# CKP_CMP.net
KiCad netlist of a schematic drawn in Altium Designer
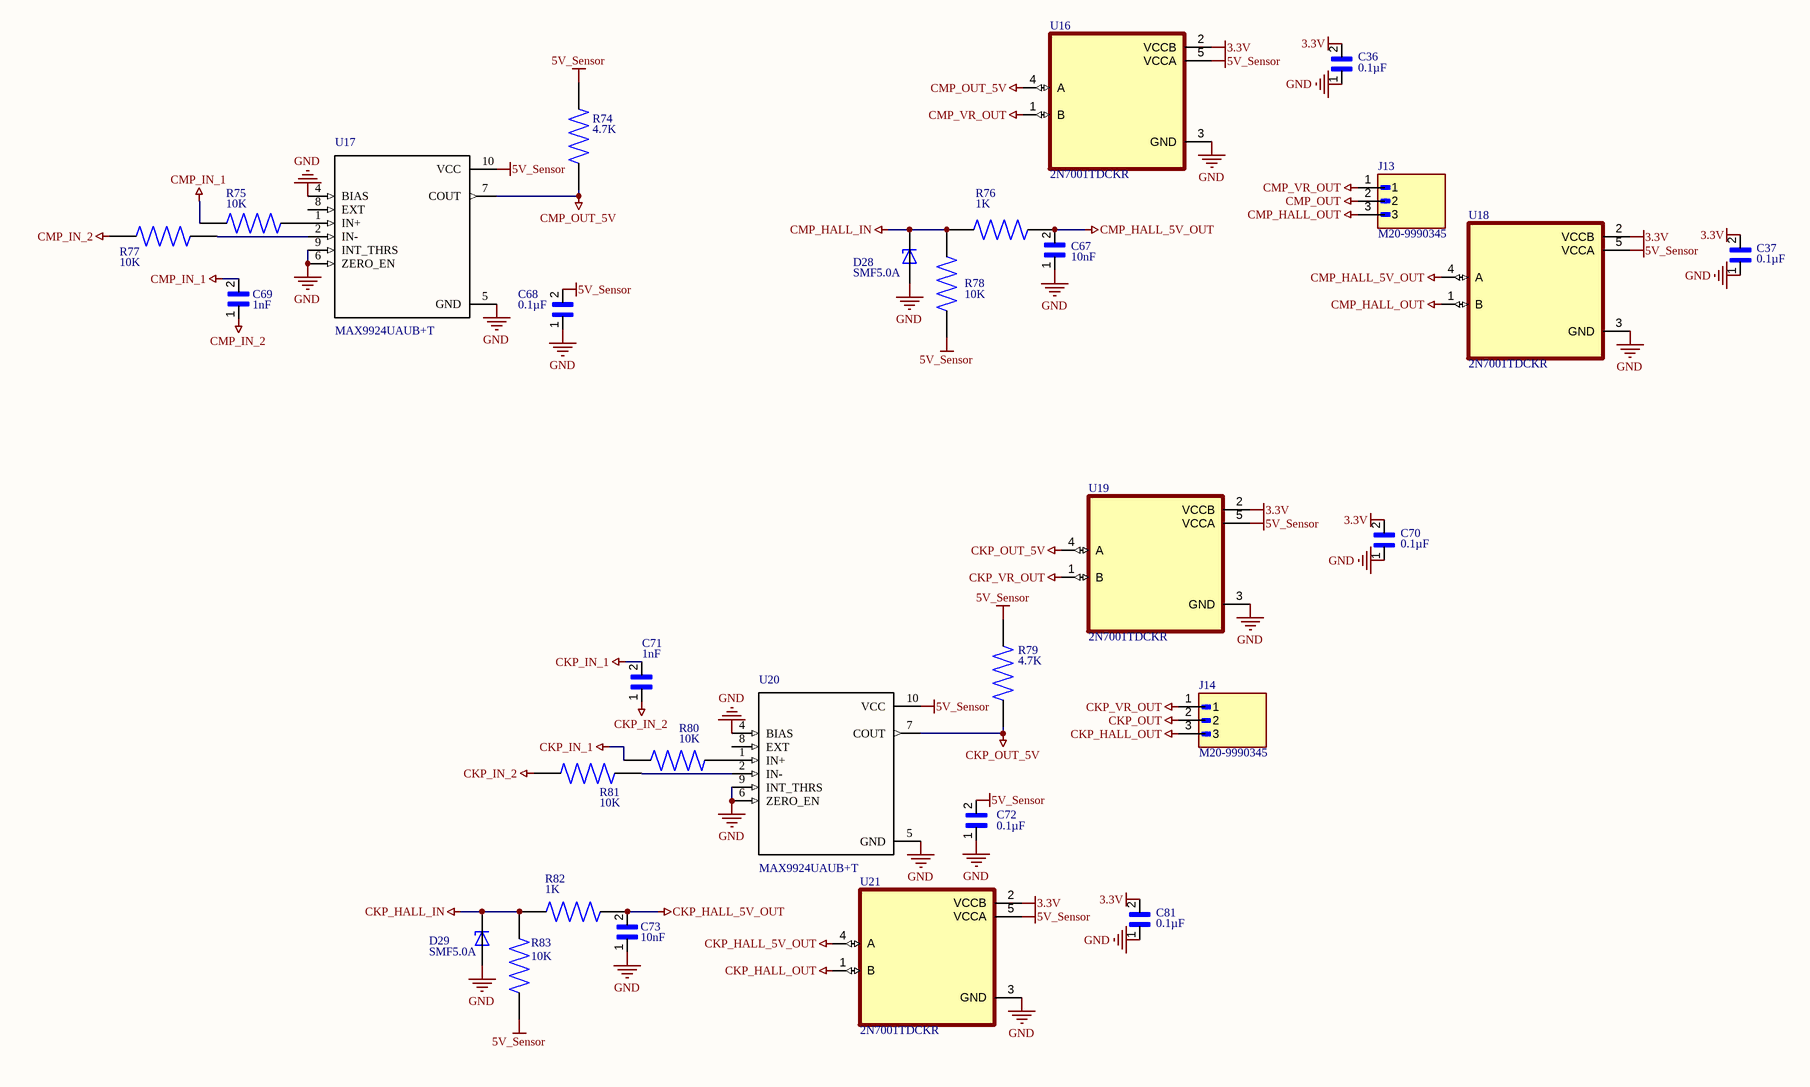
[diagram p0: CKP_CMP.SchDoc]

(export (version "E")
  (design (tool "Eeschema 10.0.6"))
  (components
    (comp (ref "C36")
      (value "0.1µF")
      (footprint "CAPC1608X90N")
      (description "Multilayer Ceramic Capacitors MLCC - SMD/SMT")
      (fields (field (name "MP") "06035C104MAZ2A"))
      (libsource (lib "06035C104MAZ2A") (part "06035C104MAZ2A"))
    )
    (comp (ref "C37")
      (value "0.1µF")
      (footprint "CAPC1608X90N")
      (description "Multilayer Ceramic Capacitors MLCC - SMD/SMT")
      (fields (field (name "MP") "06035C104MAZ2A"))
      (libsource (lib "06035C104MAZ2A") (part "06035C104MAZ2A"))
    )
    (comp (ref "C67")
      (value "10nF")
      (footprint "CAPC1608X90N")
      (description "Multilayer Ceramic Capacitors MLCC - SMD/SMT")
      (fields (field (name "MP") "06035C104MAZ2A"))
      (libsource (lib "06035C104MAZ2A") (part "06035C104MAZ2A"))
    )
    (comp (ref "C68")
      (value "0.1µF")
      (footprint "CAPC1608X90N")
      (description "Multilayer Ceramic Capacitors MLCC - SMD/SMT")
      (fields (field (name "MP") "06035C104MAZ2A"))
      (libsource (lib "06035C104MAZ2A") (part "06035C104MAZ2A"))
    )
    (comp (ref "C69")
      (value "1nF")
      (footprint "CAPC1608X90N")
      (description "Multilayer Ceramic Capacitors MLCC - SMD/SMT")
      (fields (field (name "MP") "06035C104MAZ2A"))
      (libsource (lib "06035C104MAZ2A") (part "06035C104MAZ2A"))
    )
    (comp (ref "C70")
      (value "0.1µF")
      (footprint "CAPC1608X90N")
      (description "Multilayer Ceramic Capacitors MLCC - SMD/SMT")
      (fields (field (name "MP") "06035C104MAZ2A"))
      (libsource (lib "06035C104MAZ2A") (part "06035C104MAZ2A"))
    )
    (comp (ref "C71")
      (value "1nF")
      (footprint "CAPC1608X90N")
      (description "Multilayer Ceramic Capacitors MLCC - SMD/SMT")
      (fields (field (name "MP") "06035C104MAZ2A"))
      (libsource (lib "06035C104MAZ2A") (part "06035C104MAZ2A"))
    )
    (comp (ref "C72")
      (value "0.1µF")
      (footprint "CAPC1608X90N")
      (description "Multilayer Ceramic Capacitors MLCC - SMD/SMT")
      (fields (field (name "MP") "06035C104MAZ2A"))
      (libsource (lib "06035C104MAZ2A") (part "06035C104MAZ2A"))
    )
    (comp (ref "C73")
      (value "10nF")
      (footprint "CAPC1608X90N")
      (description "Multilayer Ceramic Capacitors MLCC - SMD/SMT")
      (fields (field (name "MP") "06035C104MAZ2A"))
      (libsource (lib "06035C104MAZ2A") (part "06035C104MAZ2A"))
    )
    (comp (ref "C81")
      (value "0.1µF")
      (footprint "CAPC1608X90N")
      (description "Multilayer Ceramic Capacitors MLCC - SMD/SMT")
      (fields (field (name "MP") "06035C104MAZ2A"))
      (libsource (lib "06035C104MAZ2A") (part "06035C104MAZ2A"))
    )
    (comp (ref "D28")
      (value "SMF5.0A")
      (footprint "SODFL3718X102N")
      (description "200W, 6.7V, 5%, Unidirectional, TVS")
      (fields (field (name "MF") "Taiwan Semiconductor"))
      (libsource (lib "SMF5.0A") (part "SMF5.0A"))
    )
    (comp (ref "D29")
      (value "SMF5.0A")
      (footprint "SODFL3718X102N")
      (description "200W, 6.7V, 5%, Unidirectional, TVS")
      (fields (field (name "MF") "Taiwan Semiconductor"))
      (libsource (lib "SMF5.0A") (part "SMF5.0A"))
    )
    (comp (ref "J13")
      (value "M20-9990345")
      (footprint "HARWIN_M20-9990345")
      (fields (field (name "MF") "Harwin"))
      (libsource (lib "M20-9990345") (part "M20-9990345"))
    )
    (comp (ref "J14")
      (value "M20-9990345")
      (footprint "HARWIN_M20-9990345")
      (fields (field (name "MF") "Harwin"))
      (libsource (lib "M20-9990345") (part "M20-9990345"))
    )
    (comp (ref "R74")
      (value "4.7K")
      (footprint "RESC3116X65N")
      (fields (field (name "MP") "AA1206JR-07470RL"))
      (libsource (lib "AA1206JR-07470RL") (part "AA1206JR-07470RL"))
    )
    (comp (ref "R75")
      (value "10K")
      (footprint "RESC3116X65N")
      (fields (field (name "MP") "AA1206JR-07470RL"))
      (libsource (lib "AA1206JR-07470RL") (part "AA1206JR-07470RL"))
    )
    (comp (ref "R76")
      (value "1K")
      (footprint "RESC3116X65N")
      (fields (field (name "MP") "AA1206JR-07470RL"))
      (libsource (lib "AA1206JR-07470RL") (part "AA1206JR-07470RL"))
    )
    (comp (ref "R77")
      (value "10K")
      (footprint "RESC3116X65N")
      (fields (field (name "MP") "AA1206JR-07470RL"))
      (libsource (lib "AA1206JR-07470RL") (part "AA1206JR-07470RL"))
    )
    (comp (ref "R78")
      (value "10K")
      (footprint "RESC3116X65N")
      (fields (field (name "MP") "AA1206JR-07470RL"))
      (libsource (lib "AA1206JR-07470RL") (part "AA1206JR-07470RL"))
    )
    (comp (ref "R79")
      (value "4.7K")
      (footprint "RESC3116X65N")
      (fields (field (name "MP") "AA1206JR-07470RL"))
      (libsource (lib "AA1206JR-07470RL") (part "AA1206JR-07470RL"))
    )
    (comp (ref "R80")
      (value "10K")
      (footprint "RESC3116X65N")
      (fields (field (name "MP") "AA1206JR-07470RL"))
      (libsource (lib "AA1206JR-07470RL") (part "AA1206JR-07470RL"))
    )
    (comp (ref "R81")
      (value "10K")
      (footprint "RESC3116X65N")
      (fields (field (name "MP") "AA1206JR-07470RL"))
      (libsource (lib "AA1206JR-07470RL") (part "AA1206JR-07470RL"))
    )
    (comp (ref "R82")
      (value "1K")
      (footprint "RESC3116X65N")
      (fields (field (name "MP") "AA1206JR-07470RL"))
      (libsource (lib "AA1206JR-07470RL") (part "AA1206JR-07470RL"))
    )
    (comp (ref "R83")
      (value "10K")
      (footprint "RESC3116X65N")
      (fields (field (name "MP") "AA1206JR-07470RL"))
      (libsource (lib "AA1206JR-07470RL") (part "AA1206JR-07470RL"))
    )
    (comp (ref "U16")
      (value "2N7001TDCKR")
      (footprint "SOT65P210X110-5N")
      (description "1-bit dual-supply buffered voltage signal converter")
      (fields (field (name "MF") "Texas Instruments"))
      (libsource (lib "2N7001TDCKR") (part "2N7001TDCKR"))
    )
    (comp (ref "U17")
      (value "MAX9924UAUB+T")
      (footprint "*SOP50P490X110-10N")
      (libsource (lib "MAX9924UAUB_T") (part "MAX9924UAUB+T"))
    )
    (comp (ref "U18")
      (value "2N7001TDCKR")
      (footprint "SOT65P210X110-5N")
      (description "1-bit dual-supply buffered voltage signal converter")
      (fields (field (name "MF") "Texas Instruments"))
      (libsource (lib "2N7001TDCKR") (part "2N7001TDCKR"))
    )
    (comp (ref "U19")
      (value "2N7001TDCKR")
      (footprint "SOT65P210X110-5N")
      (description "1-bit dual-supply buffered voltage signal converter")
      (fields (field (name "MF") "Texas Instruments"))
      (libsource (lib "2N7001TDCKR") (part "2N7001TDCKR"))
    )
    (comp (ref "U20")
      (value "MAX9924UAUB+T")
      (footprint "*SOP50P490X110-10N")
      (libsource (lib "MAX9924UAUB_T") (part "MAX9924UAUB+T"))
    )
    (comp (ref "U21")
      (value "2N7001TDCKR")
      (footprint "SOT65P210X110-5N")
      (description "1-bit dual-supply buffered voltage signal converter")
      (fields (field (name "MF") "Texas Instruments"))
      (libsource (lib "2N7001TDCKRa") (part "2N7001TDCKR"))
    )
  )
  (nets
    (net (code "1") (name "3.3V") (class "Default")
      (node (ref "C36") (pin "2") (pinfunction "2_2") (pintype "passive"))
      (node (ref "C37") (pin "2") (pinfunction "2_2") (pintype "passive"))
      (node (ref "C70") (pin "2") (pinfunction "2_2") (pintype "passive"))
      (node (ref "C81") (pin "2") (pinfunction "2_2") (pintype "passive"))
      (node (ref "U16") (pin "2") (pinfunction "VCCB_2") (pintype "power_in"))
      (node (ref "U18") (pin "2") (pinfunction "VCCB_2") (pintype "power_in"))
      (node (ref "U19") (pin "2") (pinfunction "VCCB_2") (pintype "power_in"))
      (node (ref "U21") (pin "2") (pinfunction "VCCB_2") (pintype "power_in"))
    )
    (net (code "2") (name "5V_Sensor") (class "Default")
      (node (ref "C68") (pin "2") (pinfunction "2_2") (pintype "passive"))
      (node (ref "C72") (pin "2") (pinfunction "2_2") (pintype "passive"))
      (node (ref "R74") (pin "2") (pinfunction "2_2") (pintype "passive"))
      (node (ref "R78") (pin "1") (pinfunction "1_1") (pintype "passive"))
      (node (ref "R79") (pin "2") (pinfunction "2_2") (pintype "passive"))
      (node (ref "R83") (pin "1") (pinfunction "1_1") (pintype "passive"))
      (node (ref "U16") (pin "5") (pinfunction "VCCA_5") (pintype "power_in"))
      (node (ref "U17") (pin "10") (pinfunction "VCC_10") (pintype "power_in"))
      (node (ref "U18") (pin "5") (pinfunction "VCCA_5") (pintype "power_in"))
      (node (ref "U19") (pin "5") (pinfunction "VCCA_5") (pintype "power_in"))
      (node (ref "U20") (pin "10") (pinfunction "VCC_10") (pintype "power_in"))
      (node (ref "U21") (pin "5") (pinfunction "VCCA_5") (pintype "power_in"))
    )
    (net (code "3") (name "CKP_HALL_5V_OUT") (class "Default")
      (node (ref "C73") (pin "2") (pinfunction "2_2") (pintype "passive"))
      (node (ref "R82") (pin "1") (pinfunction "1_1") (pintype "passive"))
      (node (ref "U21") (pin "4") (pinfunction "A_4") (pintype "bidirectional"))
    )
    (net (code "4") (name "CKP_HALL_IN") (class "Default")
      (node (ref "D29") (pin "C") (pinfunction "C_C") (pintype "passive"))
      (node (ref "R82") (pin "2") (pinfunction "2_2") (pintype "passive"))
      (node (ref "R83") (pin "2") (pinfunction "2_2") (pintype "passive"))
    )
    (net (code "5") (name "CKP_HALL_OUT") (class "Default")
      (node (ref "J14") (pin "3") (pinfunction "3_3") (pintype "passive"))
      (node (ref "U21") (pin "1") (pinfunction "B_1") (pintype "bidirectional"))
    )
    (net (code "6") (name "CKP_IN_1") (class "Default")
      (node (ref "C71") (pin "2") (pinfunction "2_2") (pintype "passive"))
      (node (ref "R80") (pin "1") (pinfunction "1_1") (pintype "passive"))
    )
    (net (code "7") (name "CKP_IN_2") (class "Default")
      (node (ref "C71") (pin "1") (pinfunction "1_1") (pintype "passive"))
      (node (ref "R81") (pin "1") (pinfunction "1_1") (pintype "passive"))
    )
    (net (code "8") (name "CKP_OUT") (class "Default")
      (node (ref "J14") (pin "2") (pinfunction "2_2") (pintype "passive"))
    )
    (net (code "9") (name "CKP_OUT_5V") (class "Default")
      (node (ref "R79") (pin "1") (pinfunction "1_1") (pintype "passive"))
      (node (ref "U19") (pin "4") (pinfunction "A_4") (pintype "bidirectional"))
      (node (ref "U20") (pin "7") (pinfunction "COUT_7") (pintype "output"))
    )
    (net (code "10") (name "CKP_VR_OUT") (class "Default")
      (node (ref "J14") (pin "1") (pinfunction "1_1") (pintype "passive"))
      (node (ref "U19") (pin "1") (pinfunction "B_1") (pintype "bidirectional"))
    )
    (net (code "11") (name "CMP_HALL_5V_OUT") (class "Default")
      (node (ref "C67") (pin "2") (pinfunction "2_2") (pintype "passive"))
      (node (ref "R76") (pin "1") (pinfunction "1_1") (pintype "passive"))
      (node (ref "U18") (pin "4") (pinfunction "A_4") (pintype "bidirectional"))
    )
    (net (code "12") (name "CMP_HALL_IN") (class "Default")
      (node (ref "D28") (pin "C") (pinfunction "C_C") (pintype "passive"))
      (node (ref "R76") (pin "2") (pinfunction "2_2") (pintype "passive"))
      (node (ref "R78") (pin "2") (pinfunction "2_2") (pintype "passive"))
    )
    (net (code "13") (name "CMP_HALL_OUT") (class "Default")
      (node (ref "J13") (pin "3") (pinfunction "3_3") (pintype "passive"))
      (node (ref "U18") (pin "1") (pinfunction "B_1") (pintype "bidirectional"))
    )
    (net (code "14") (name "CMP_IN_1") (class "Default")
      (node (ref "C69") (pin "2") (pinfunction "2_2") (pintype "passive"))
      (node (ref "R75") (pin "1") (pinfunction "1_1") (pintype "passive"))
    )
    (net (code "15") (name "CMP_IN_2") (class "Default")
      (node (ref "C69") (pin "1") (pinfunction "1_1") (pintype "passive"))
      (node (ref "R77") (pin "1") (pinfunction "1_1") (pintype "passive"))
    )
    (net (code "16") (name "CMP_OUT") (class "Default")
      (node (ref "J13") (pin "2") (pinfunction "2_2") (pintype "passive"))
    )
    (net (code "17") (name "CMP_OUT_5V") (class "Default")
      (node (ref "R74") (pin "1") (pinfunction "1_1") (pintype "passive"))
      (node (ref "U16") (pin "4") (pinfunction "A_4") (pintype "bidirectional"))
      (node (ref "U17") (pin "7") (pinfunction "COUT_7") (pintype "output"))
    )
    (net (code "18") (name "CMP_VR_OUT") (class "Default")
      (node (ref "J13") (pin "1") (pinfunction "1_1") (pintype "passive"))
      (node (ref "U16") (pin "1") (pinfunction "B_1") (pintype "bidirectional"))
    )
    (net (code "19") (name "GND") (class "Default")
      (node (ref "C36") (pin "1") (pinfunction "1_1") (pintype "passive"))
      (node (ref "C37") (pin "1") (pinfunction "1_1") (pintype "passive"))
      (node (ref "C67") (pin "1") (pinfunction "1_1") (pintype "passive"))
      (node (ref "C68") (pin "1") (pinfunction "1_1") (pintype "passive"))
      (node (ref "C70") (pin "1") (pinfunction "1_1") (pintype "passive"))
      (node (ref "C72") (pin "1") (pinfunction "1_1") (pintype "passive"))
      (node (ref "C73") (pin "1") (pinfunction "1_1") (pintype "passive"))
      (node (ref "C81") (pin "1") (pinfunction "1_1") (pintype "passive"))
      (node (ref "D28") (pin "A") (pinfunction "A_A") (pintype "passive"))
      (node (ref "D29") (pin "A") (pinfunction "A_A") (pintype "passive"))
      (node (ref "U16") (pin "3") (pinfunction "GND_3") (pintype "power_in"))
      (node (ref "U17") (pin "4") (pinfunction "BIAS_4") (pintype "input"))
      (node (ref "U17") (pin "5") (pinfunction "GND_5") (pintype "power_in"))
      (node (ref "U17") (pin "6") (pinfunction "ZERO_EN_6") (pintype "input"))
      (node (ref "U17") (pin "9") (pinfunction "INT_THRS_9") (pintype "input"))
      (node (ref "U18") (pin "3") (pinfunction "GND_3") (pintype "power_in"))
      (node (ref "U19") (pin "3") (pinfunction "GND_3") (pintype "power_in"))
      (node (ref "U20") (pin "4") (pinfunction "BIAS_4") (pintype "input"))
      (node (ref "U20") (pin "5") (pinfunction "GND_5") (pintype "power_in"))
      (node (ref "U20") (pin "6") (pinfunction "ZERO_EN_6") (pintype "input"))
      (node (ref "U20") (pin "9") (pinfunction "INT_THRS_9") (pintype "input"))
      (node (ref "U21") (pin "3") (pinfunction "GND_3") (pintype "power_in"))
    )
    (net (code "20") (name "Net-(U17-IN+)") (class "Default")
      (node (ref "R75") (pin "2") (pinfunction "2_2") (pintype "passive"))
      (node (ref "U17") (pin "1") (pinfunction "IN+_1") (pintype "input"))
    )
    (net (code "21") (name "Net-(U17-IN-)") (class "Default")
      (node (ref "R77") (pin "2") (pinfunction "2_2") (pintype "passive"))
      (node (ref "U17") (pin "2") (pinfunction "IN-_2") (pintype "input"))
    )
    (net (code "22") (name "Net-(U20-IN+)") (class "Default")
      (node (ref "R80") (pin "2") (pinfunction "2_2") (pintype "passive"))
      (node (ref "U20") (pin "1") (pinfunction "IN+_1") (pintype "input"))
    )
    (net (code "23") (name "Net-(U20-IN-)") (class "Default")
      (node (ref "R81") (pin "2") (pinfunction "2_2") (pintype "passive"))
      (node (ref "U20") (pin "2") (pinfunction "IN-_2") (pintype "input"))
    )
    (net (code "24") (name "unconnected-(U17-EXT-Pad8)") (class "Default")
      (node (ref "U17") (pin "8") (pinfunction "EXT_8") (pintype "input"))
    )
    (net (code "25") (name "unconnected-(U20-EXT-Pad8)") (class "Default")
      (node (ref "U20") (pin "8") (pinfunction "EXT_8") (pintype "input"))
    )
  )
)
